# LEDALPanel.net
KiCad netlist of a schematic drawn in EAGLE
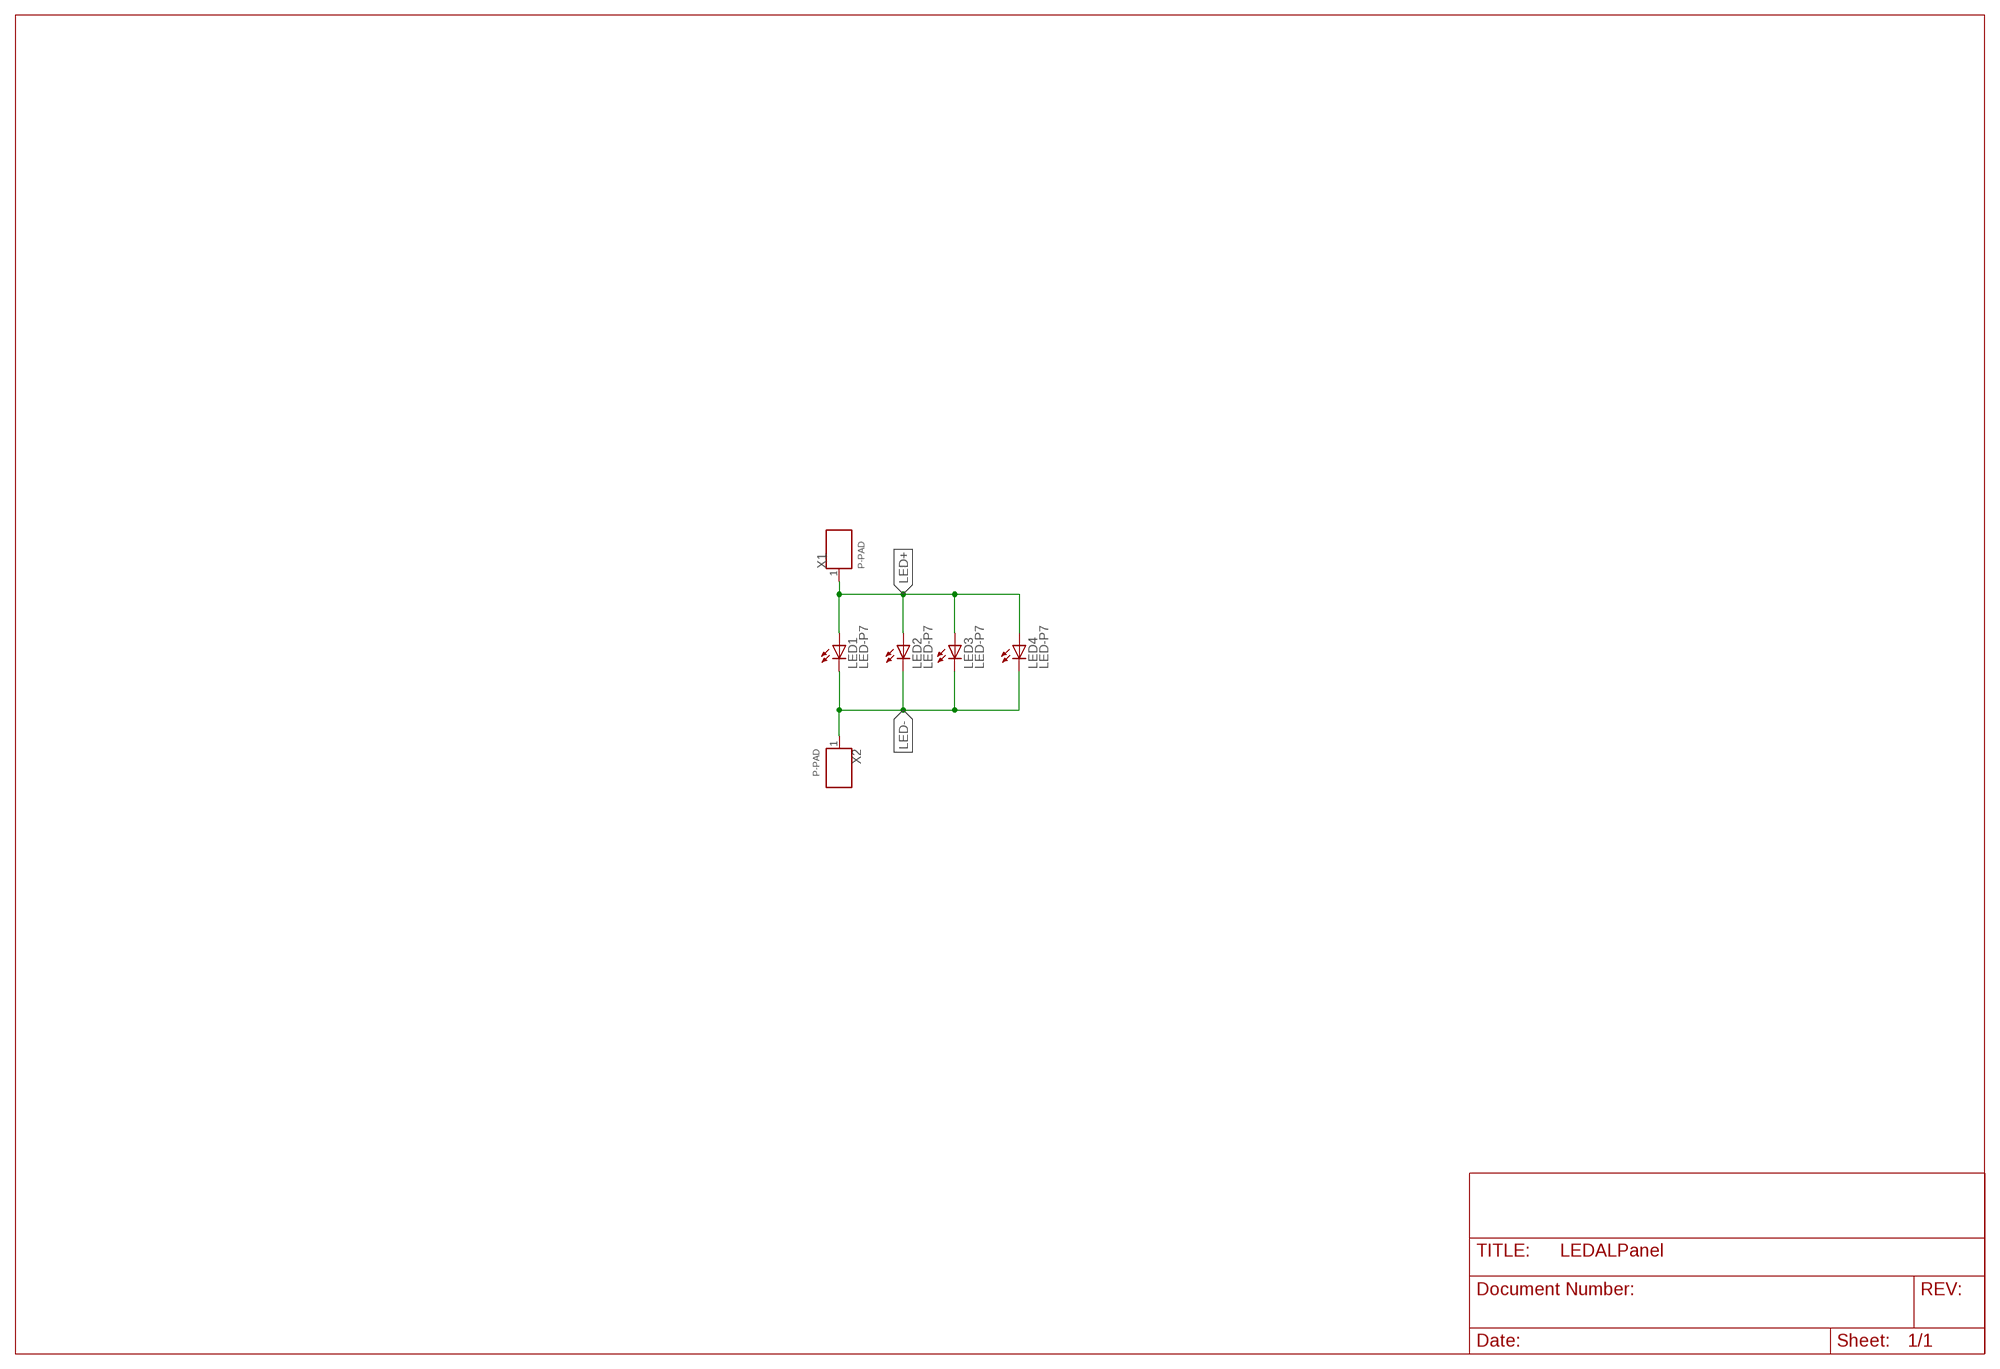
[diagram p0: schematic, sheet 1]

(export (version "E")
  (design (tool "Eeschema 10.0.6"))
  (components
    (comp (ref "LED1")
      (value "LED-P7")
      (footprint "eagle-import:P7")
      (libsource (lib "eagle-import") (part "LED-P7"))
    )
    (comp (ref "LED2")
      (value "LED-P7")
      (footprint "eagle-import:P7")
      (libsource (lib "eagle-import") (part "LED-P7"))
    )
    (comp (ref "LED3")
      (value "LED-P7")
      (footprint "eagle-import:P7")
      (libsource (lib "eagle-import") (part "LED-P7"))
    )
    (comp (ref "LED4")
      (value "LED-P7")
      (footprint "eagle-import:P7")
      (libsource (lib "eagle-import") (part "LED-P7"))
    )
    (comp (ref "X1")
      (value "P-PAD")
      (footprint "eagle-import:P-PAD")
      (libsource (lib "eagle-import") (part "P-PAD"))
    )
    (comp (ref "X2")
      (value "P-PAD")
      (footprint "eagle-import:P-PAD")
      (libsource (lib "eagle-import") (part "P-PAD"))
    )
  )
  (nets
    (net (code "1") (name "LED+") (class "Default")
      (node (ref "LED1") (pin "A") (pinfunction "A_A") (pintype "passive"))
      (node (ref "LED2") (pin "A") (pinfunction "A_A") (pintype "passive"))
      (node (ref "LED3") (pin "A") (pinfunction "A_A") (pintype "passive"))
      (node (ref "LED4") (pin "A") (pinfunction "A_A") (pintype "passive"))
      (node (ref "X1") (pin "1") (pinfunction "P$1_1") (pintype "bidirectional"))
    )
    (net (code "2") (name "LED-") (class "Default")
      (node (ref "LED1") (pin "C") (pinfunction "C_C") (pintype "passive"))
      (node (ref "LED2") (pin "C") (pinfunction "C_C") (pintype "passive"))
      (node (ref "LED3") (pin "C") (pinfunction "C_C") (pintype "passive"))
      (node (ref "LED4") (pin "C") (pinfunction "C_C") (pintype "passive"))
      (node (ref "X2") (pin "1") (pinfunction "P$1_1") (pintype "bidirectional"))
    )
  )
)
